# ProPrj__mini-c3_2025-12-10.net
KiCad netlist of a schematic drawn in EasyEDA Pro
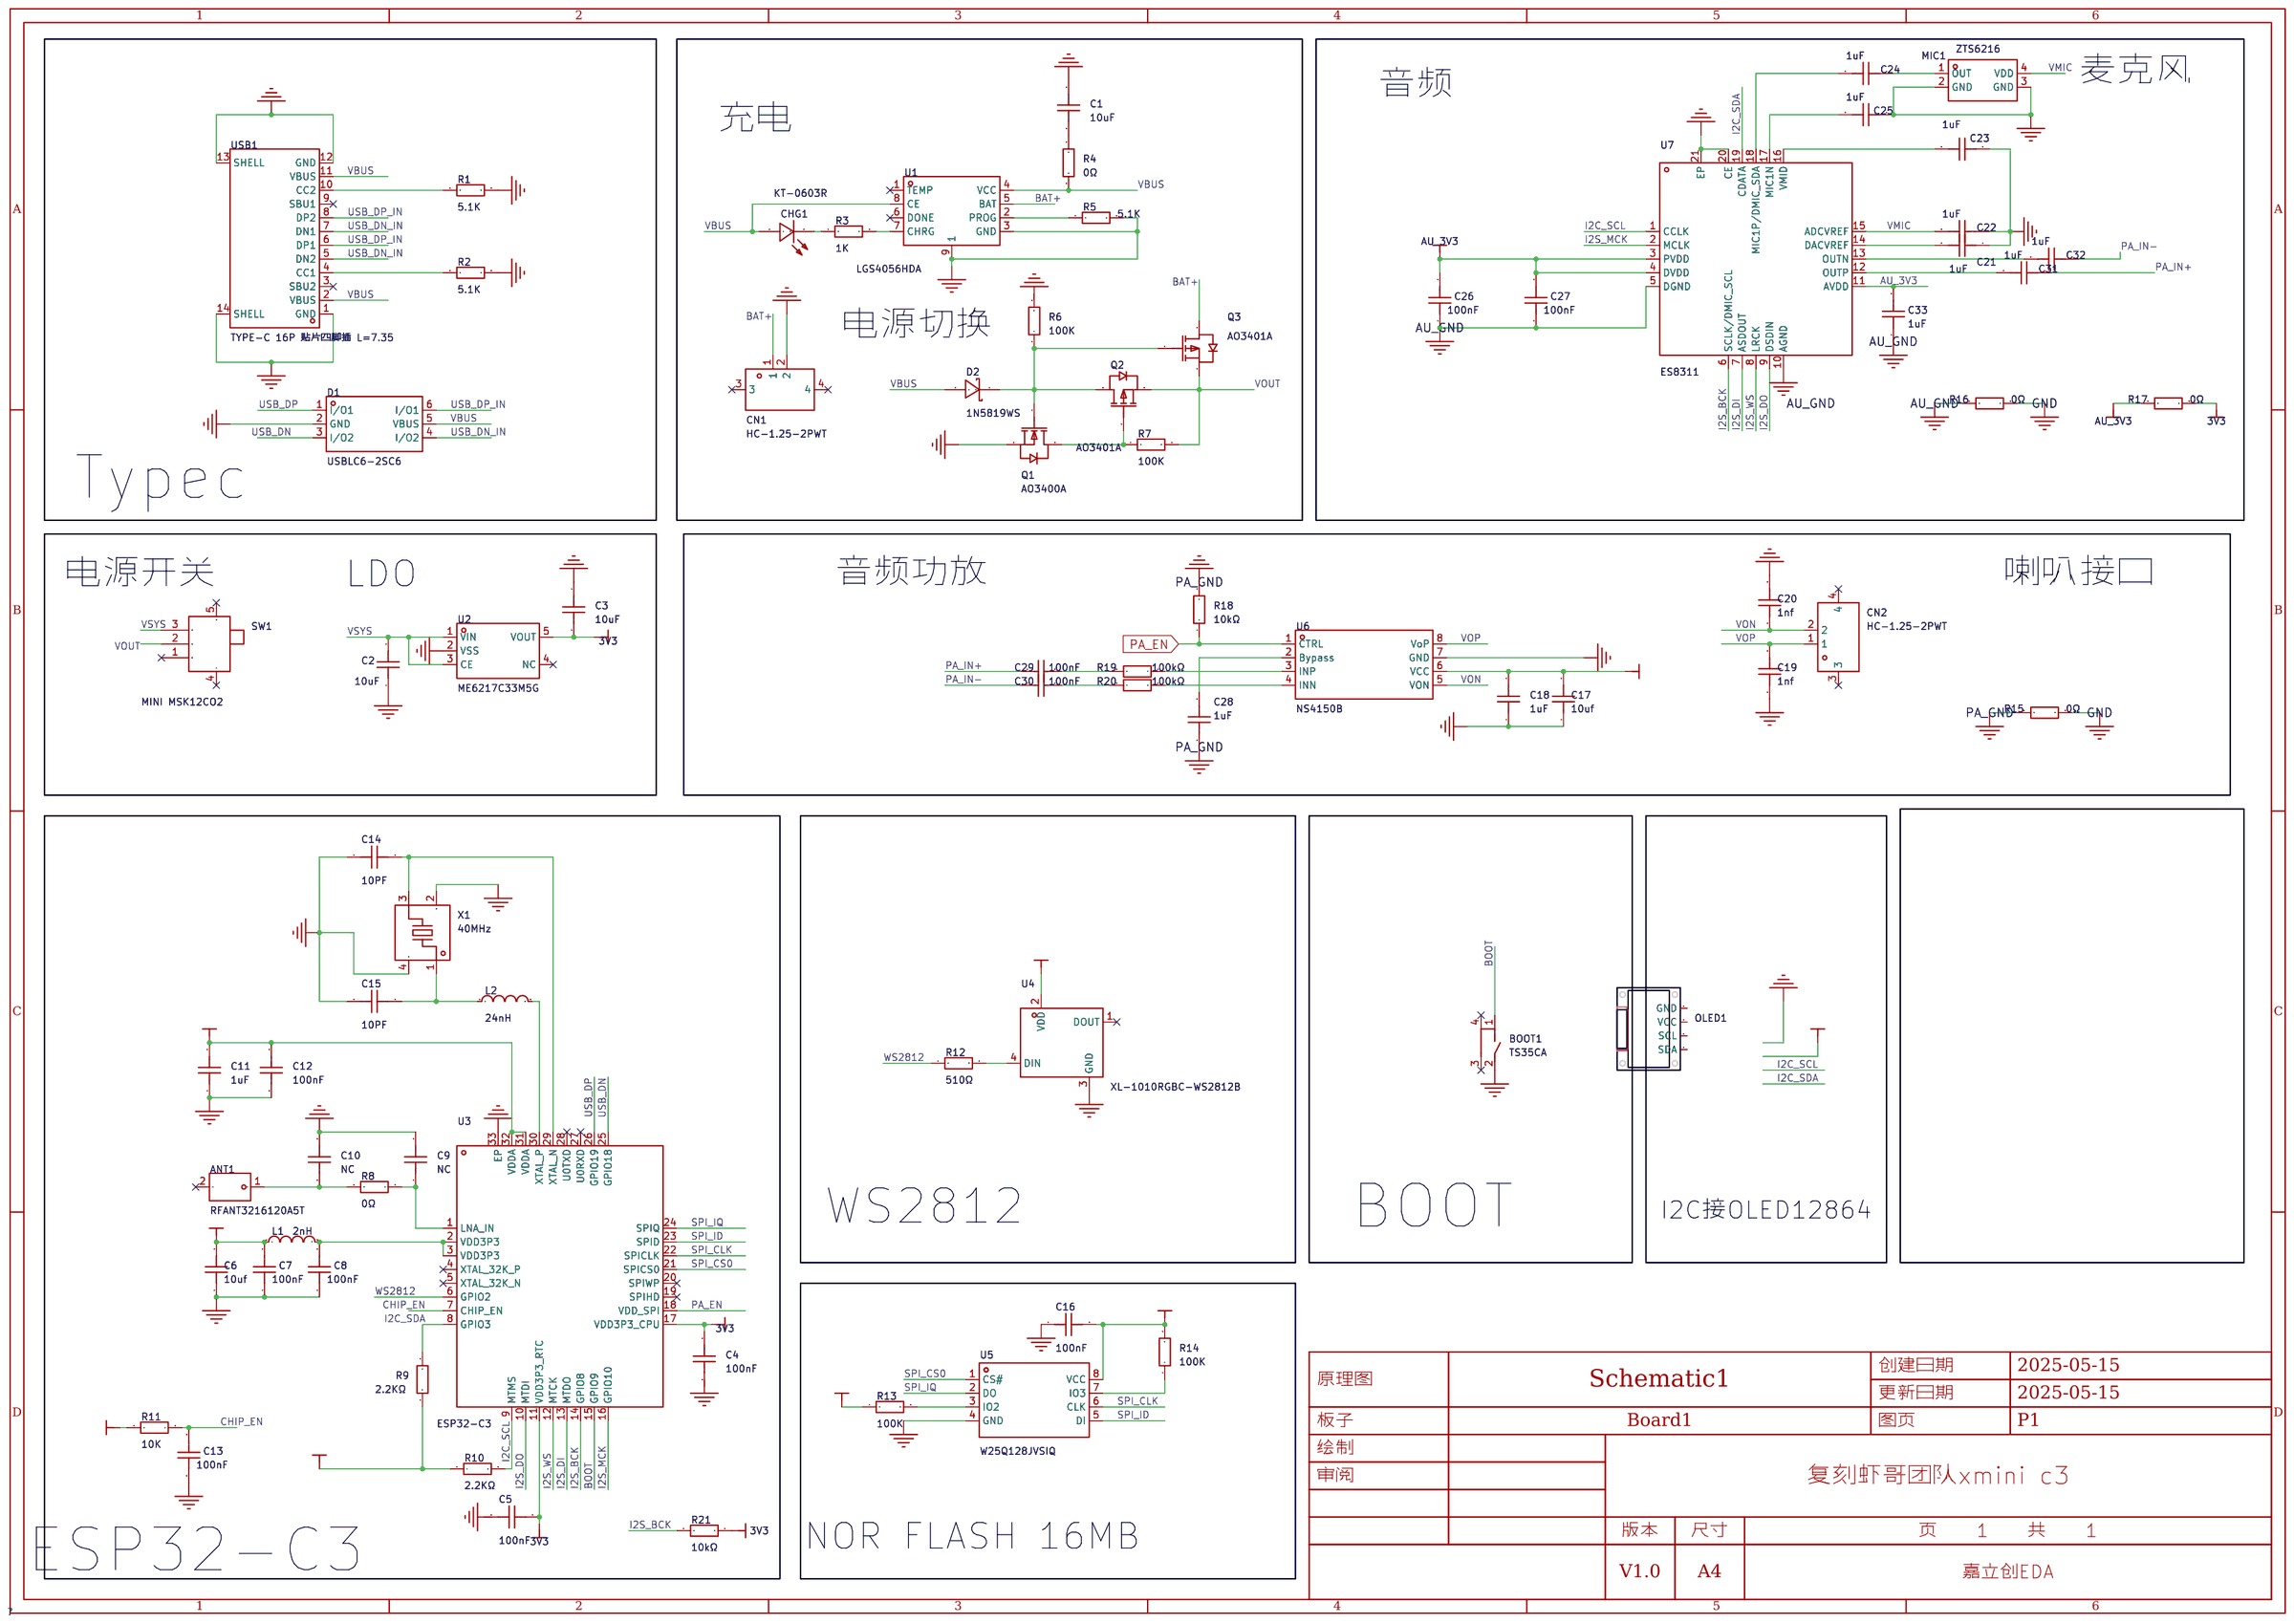
[diagram p0: schematic sheet]

(export (version "E")
  (design (tool "Eeschema 10.0.6"))
  (components
    (comp (ref "ANT1")
      (value "RFANT3216120A5T")
      (footprint "easyedapro:FILTER-SMD_1206-2P-L3.2-W1.6-L")
      (fields (field (name "Manufacturer") "Walsin(华新科)"))
      (libsource (lib "easyedapro") (part "RFANT3216120A5T"))
    )
    (comp (ref "BOOT1")
      (value "TS35CA")
      (footprint "easyedapro:KEY-SMD_TS35CA")
      (fields (field (name "Manufacturer") "SHOU HAN(首韩)"))
      (libsource (lib "easyedapro") (part "TS35CA"))
    )
    (comp (ref "C1")
      (value "10uF")
      (footprint "easyedapro:C0402")
      (libsource (lib "easyedapro") (part "CapAcitance"))
    )
    (comp (ref "C2")
      (value "10uF")
      (footprint "easyedapro:C0402")
      (libsource (lib "easyedapro") (part "CapAcitance"))
    )
    (comp (ref "C3")
      (value "10uF")
      (footprint "easyedapro:C0402")
      (libsource (lib "easyedapro") (part "CapAcitance"))
    )
    (comp (ref "C4")
      (value "100nF")
      (footprint "easyedapro:C0402")
      (libsource (lib "easyedapro") (part "CapAcitance"))
    )
    (comp (ref "C5")
      (value "100nF")
      (footprint "easyedapro:C0402")
      (libsource (lib "easyedapro") (part "CapAcitance"))
    )
    (comp (ref "C6")
      (value "10uf")
      (footprint "easyedapro:C0402")
      (libsource (lib "easyedapro") (part "CapAcitance"))
    )
    (comp (ref "C7")
      (value "100nF")
      (footprint "easyedapro:C0402")
      (libsource (lib "easyedapro") (part "CapAcitance"))
    )
    (comp (ref "C8")
      (value "100nF")
      (footprint "easyedapro:C0402")
      (libsource (lib "easyedapro") (part "CapAcitance"))
    )
    (comp (ref "C9")
      (value "NC")
      (footprint "easyedapro:C0402")
      (libsource (lib "easyedapro") (part "CapAcitance"))
    )
    (comp (ref "C10")
      (value "NC")
      (footprint "easyedapro:C0402")
      (libsource (lib "easyedapro") (part "CapAcitance"))
    )
    (comp (ref "C11")
      (value "1uF")
      (footprint "easyedapro:C0402")
      (libsource (lib "easyedapro") (part "CapAcitance"))
    )
    (comp (ref "C12")
      (value "100nF")
      (footprint "easyedapro:C0402")
      (libsource (lib "easyedapro") (part "CapAcitance"))
    )
    (comp (ref "C13")
      (value "100nF")
      (footprint "easyedapro:C0402")
      (libsource (lib "easyedapro") (part "CapAcitance"))
    )
    (comp (ref "C14")
      (value "10PF")
      (footprint "easyedapro:C0402")
      (libsource (lib "easyedapro") (part "CapAcitance"))
    )
    (comp (ref "C15")
      (value "10PF")
      (footprint "easyedapro:C0402")
      (libsource (lib "easyedapro") (part "CapAcitance"))
    )
    (comp (ref "C16")
      (value "100nF")
      (footprint "easyedapro:C0402")
      (libsource (lib "easyedapro") (part "CapAcitance"))
    )
    (comp (ref "C17")
      (value "10uf")
      (footprint "easyedapro:C0402")
      (libsource (lib "easyedapro") (part "CapAcitance"))
    )
    (comp (ref "C18")
      (value "1uF")
      (footprint "easyedapro:C0402")
      (libsource (lib "easyedapro") (part "CapAcitance"))
    )
    (comp (ref "C19")
      (value "1nf")
      (footprint "easyedapro:C0402")
      (libsource (lib "easyedapro") (part "CapAcitance"))
    )
    (comp (ref "C20")
      (value "1nf")
      (footprint "easyedapro:C0402")
      (libsource (lib "easyedapro") (part "CapAcitance"))
    )
    (comp (ref "C21")
      (value "1uF")
      (footprint "easyedapro:C0402")
      (libsource (lib "easyedapro") (part "CapAcitance"))
    )
    (comp (ref "C22")
      (value "1uF")
      (footprint "easyedapro:C0402")
      (libsource (lib "easyedapro") (part "CapAcitance"))
    )
    (comp (ref "C23")
      (value "1uF")
      (footprint "easyedapro:C0402")
      (libsource (lib "easyedapro") (part "CapAcitance"))
    )
    (comp (ref "C24")
      (value "1uF")
      (footprint "easyedapro:C0402")
      (libsource (lib "easyedapro") (part "CapAcitance"))
    )
    (comp (ref "C25")
      (value "1uF")
      (footprint "easyedapro:C0402")
      (libsource (lib "easyedapro") (part "CapAcitance"))
    )
    (comp (ref "C26")
      (value "100nF")
      (footprint "easyedapro:C0402")
      (libsource (lib "easyedapro") (part "CapAcitance"))
    )
    (comp (ref "C27")
      (value "100nF")
      (footprint "easyedapro:C0402")
      (libsource (lib "easyedapro") (part "CapAcitance"))
    )
    (comp (ref "C28")
      (value "1uF")
      (footprint "easyedapro:C0402")
      (fields
        (field (name "Manufacturer Part") "CL05A105KA5NQNC")
        (field (name "Manufacturer") "SAMSUNG(三星)")
      )
      (libsource (lib "easyedapro") (part "CL05A105KA5NQNC"))
    )
    (comp (ref "C29")
      (value "100nF")
      (footprint "easyedapro:C0402")
      (fields
        (field (name "Manufacturer Part") "CL05B104KO5NNNC")
        (field (name "Manufacturer") "SAMSUNG(三星)")
      )
      (libsource (lib "easyedapro") (part "CL05B104KO5NNNC"))
    )
    (comp (ref "C30")
      (value "100nF")
      (footprint "easyedapro:C0402")
      (fields
        (field (name "Manufacturer Part") "CL05B104KO5NNNC")
        (field (name "Manufacturer") "SAMSUNG(三星)")
      )
      (libsource (lib "easyedapro") (part "CL05B104KO5NNNC"))
    )
    (comp (ref "C31")
      (value "1uF")
      (footprint "easyedapro:C0402")
      (libsource (lib "easyedapro") (part "CapAcitance"))
    )
    (comp (ref "C32")
      (value "1uF")
      (footprint "easyedapro:C0402")
      (libsource (lib "easyedapro") (part "CapAcitance"))
    )
    (comp (ref "C33")
      (value "1uF")
      (footprint "easyedapro:C0402")
      (fields
        (field (name "Manufacturer Part") "CL05A105KA5NQNC")
        (field (name "Manufacturer") "SAMSUNG(三星)")
      )
      (libsource (lib "easyedapro") (part "CL05A105KA5NQNC"))
    )
    (comp (ref "CHG1")
      (value "KT-0603R")
      (footprint "easyedapro:LED0603-RD")
      (fields (field (name "Manufacturer") "KENTO"))
      (libsource (lib "easyedapro") (part "KT-0603R"))
    )
    (comp (ref "CN1")
      (value "HC-1.25-2PWT")
      (footprint "easyedapro:CONN-SMD_2P-P1.25-HC-1.25-2PWT")
      (fields (field (name "Manufacturer") "HCTL(华灿天禄)"))
      (libsource (lib "easyedapro") (part "HC-1.25-2PWT"))
    )
    (comp (ref "CN2")
      (value "HC-1.25-2PWT")
      (footprint "easyedapro:CONN-SMD_2P-P1.25-HC-1.25-2PWT")
      (fields (field (name "Manufacturer") "HCTL(华灿天禄)"))
      (libsource (lib "easyedapro") (part "HC-1.25-2PWT"))
    )
    (comp (ref "D1")
      (value "USBLC6-2SC6")
      (footprint "easyedapro:SOT-23-6_L2.9-W1.6-P0.95-LS2.8-BL")
      (fields (field (name "Manufacturer") "UMW(友台半导体)"))
      (libsource (lib "easyedapro") (part "USBLC6-2SC6_C2687116"))
    )
    (comp (ref "D2")
      (value "1N5819WS")
      (footprint "easyedapro:SOD-323_L1.8-W1.3-LS2.5-RD")
      (fields (field (name "Manufacturer") "Hottech(合科泰)"))
      (libsource (lib "easyedapro") (part "1N5819WS"))
    )
    (comp (ref "L1")
      (value "2nH")
      (footprint "easyedapro:L0402")
      (libsource (lib "easyedapro") (part "SDCL1005C10NJTDFM01"))
    )
    (comp (ref "L2")
      (value "24nH")
      (footprint "easyedapro:L0402")
      (libsource (lib "easyedapro") (part "SDCL1005C10NJTDFM01"))
    )
    (comp (ref "MIC1")
      (value "ZTS6216")
      (footprint "easyedapro:MIC-SMD_4P-L2.8-W1.9-P1.84-TL")
      (description "方向:全指向;信噪比:65dB;灵敏度:-38dB;阻抗:100Ω;")
      (fields (field (name "Manufacturer") "ZILLTEK(钰太)"))
      (libsource (lib "easyedapro") (part "ZTS6216"))
    )
    (comp (ref "OLED1")
      (value "~")
      (footprint "easyedapro:0.96OLED_4P")
      (libsource (lib "easyedapro") (part "0.96OLED模块_4P"))
    )
    (comp (ref "Q1")
      (value "AO3400A")
      (footprint "easyedapro:SOT-23-3_L2.9-W1.3-P1.90-LS2.4-BR")
      (fields (field (name "Manufacturer") "AOS"))
      (libsource (lib "easyedapro") (part "AO3400A"))
    )
    (comp (ref "Q2")
      (value "AO3401A")
      (footprint "easyedapro:SOT-23_L2.9-W1.3-P1.90-LS2.4-BR")
      (fields (field (name "Manufacturer") "AOS"))
      (libsource (lib "easyedapro") (part "AO3401A"))
    )
    (comp (ref "Q3")
      (value "AO3401A")
      (footprint "easyedapro:SOT-23_L2.9-W1.3-P1.90-LS2.4-BR")
      (fields (field (name "Manufacturer") "AOS"))
      (libsource (lib "easyedapro") (part "AO3401A"))
    )
    (comp (ref "R1") (value "5.1K") (footprint "easyedapro:R0402") (libsource (lib "easyedapro") (part "电阻")))
    (comp (ref "R2") (value "5.1K") (footprint "easyedapro:R0402") (libsource (lib "easyedapro") (part "电阻")))
    (comp (ref "R3") (value "1K") (footprint "easyedapro:R0402") (libsource (lib "easyedapro") (part "电阻")))
    (comp (ref "R4") (value "0Ω") (footprint "easyedapro:R0402") (libsource (lib "easyedapro") (part "电阻")))
    (comp (ref "R5") (value "5.1K") (footprint "easyedapro:R0402") (libsource (lib "easyedapro") (part "电阻")))
    (comp (ref "R6") (value "100K") (footprint "easyedapro:R0402") (libsource (lib "easyedapro") (part "电阻")))
    (comp (ref "R7") (value "100K") (footprint "easyedapro:R0402") (libsource (lib "easyedapro") (part "电阻")))
    (comp (ref "R8") (value "0Ω") (footprint "easyedapro:R0402") (libsource (lib "easyedapro") (part "电阻")))
    (comp (ref "R9")
      (value "2.2KΩ")
      (footprint "easyedapro:R0402")
      (libsource (lib "easyedapro") (part "电阻"))
    )
    (comp (ref "R10")
      (value "2.2KΩ")
      (footprint "easyedapro:R0402")
      (libsource (lib "easyedapro") (part "电阻"))
    )
    (comp (ref "R11") (value "10K") (footprint "easyedapro:R0402") (libsource (lib "easyedapro") (part "电阻")))
    (comp (ref "R12")
      (value "510Ω")
      (footprint "easyedapro:R0402")
      (libsource (lib "easyedapro") (part "电阻"))
    )
    (comp (ref "R13")
      (value "100K")
      (footprint "easyedapro:R0402")
      (libsource (lib "easyedapro") (part "电阻"))
    )
    (comp (ref "R14")
      (value "100K")
      (footprint "easyedapro:R0402")
      (libsource (lib "easyedapro") (part "电阻"))
    )
    (comp (ref "R15")
      (value "0Ω")
      (footprint "easyedapro:R0402")
      (fields
        (field (name "Manufacturer Part") "0402WGF0000TCE")
        (field (name "Manufacturer") "UNI-ROYAL(厚声)")
      )
      (libsource (lib "easyedapro") (part "0402WGF0000TCE"))
    )
    (comp (ref "R16")
      (value "0Ω")
      (footprint "easyedapro:R0402")
      (fields
        (field (name "Manufacturer Part") "0402WGF0000TCE")
        (field (name "Manufacturer") "UNI-ROYAL(厚声)")
      )
      (libsource (lib "easyedapro") (part "0402WGF0000TCE"))
    )
    (comp (ref "R17")
      (value "0Ω")
      (footprint "easyedapro:R0402")
      (fields
        (field (name "Manufacturer Part") "0402WGF0000TCE")
        (field (name "Manufacturer") "UNI-ROYAL(厚声)")
      )
      (libsource (lib "easyedapro") (part "0402WGF0000TCE"))
    )
    (comp (ref "R18")
      (value "10kΩ")
      (footprint "easyedapro:R0402")
      (fields
        (field (name "Manufacturer Part") "0402WGF1002TCE")
        (field (name "Manufacturer") "UNI-ROYAL(厚声)")
      )
      (libsource (lib "easyedapro") (part "0402WGF1002TCE"))
    )
    (comp (ref "R19")
      (value "100kΩ")
      (footprint "easyedapro:R0402")
      (fields
        (field (name "Manufacturer Part") "0402WGF1003TCE")
        (field (name "Manufacturer") "UNI-ROYAL(厚声)")
      )
      (libsource (lib "easyedapro") (part "0402WGF1003TCE"))
    )
    (comp (ref "R20")
      (value "100kΩ")
      (footprint "easyedapro:R0402")
      (fields
        (field (name "Manufacturer Part") "0402WGF1003TCE")
        (field (name "Manufacturer") "UNI-ROYAL(厚声)")
      )
      (libsource (lib "easyedapro") (part "0402WGF1003TCE"))
    )
    (comp (ref "R21")
      (value "10kΩ")
      (footprint "easyedapro:R0402")
      (fields
        (field (name "Manufacturer Part") "0402WGF1002TCE")
        (field (name "Manufacturer") "UNI-ROYAL(厚声)")
      )
      (libsource (lib "easyedapro") (part "0402WGF1002TCE"))
    )
    (comp (ref "SW1")
      (value "MINI MSK12CO2")
      (footprint "easyedapro:SW-SMD_MSK12CO2")
      (fields (field (name "Manufacturer") "SHOU HAN(首韩)"))
      (libsource (lib "easyedapro") (part "MINI MSK12CO2"))
    )
    (comp (ref "U1")
      (value "LGS4056HDA")
      (footprint "easyedapro:DFN-8_L2.0-W2.0-P0.50-TL-EP1.6")
      (fields (field (name "Manufacturer") "Legend-Si(棱晶半导体)"))
      (libsource (lib "easyedapro") (part "LGS4056H"))
    )
    (comp (ref "U2")
      (value "ME6217C33M5G")
      (footprint "easyedapro:SOT-23-5_L3.0-W1.7-P0.95-LS2.8-BR")
      (fields (field (name "Manufacturer") "MICRONE(南京微盟)"))
      (libsource (lib "easyedapro") (part "ME6217C33M5G"))
    )
    (comp (ref "U3")
      (value "ESP32-C3")
      (footprint "easyedapro:QFN-32_L5.0-W5.0-P0.50-TL-EP3.7")
      (fields (field (name "Manufacturer") "ESPRESSIF(乐鑫)"))
      (libsource (lib "easyedapro") (part "ESP32-C3"))
    )
    (comp (ref "U4")
      (value "XL-1010RGBC-WS2812B")
      (footprint "easyedapro:LED-SMD_4P-L1.0-W1.0-TL_XL-1010RGBC-WS2812B")
      (fields (field (name "Manufacturer") "XINGLIGHT(成兴光)"))
      (libsource (lib "easyedapro") (part "XL-1010RGBC-WS2812B"))
    )
    (comp (ref "U5")
      (value "W25Q128JVSIQ")
      (footprint "easyedapro:SOIC-8_L5.3-W5.3-P1.27-LS8.0-BL")
      (fields (field (name "Manufacturer") "WINBOND(华邦)"))
      (libsource (lib "easyedapro") (part "W25Q128JVSIQTR"))
    )
    (comp (ref "U6")
      (value "NS4150B")
      (footprint "easyedapro:MSOP-8_L3.0-W3.0-P0.65-LS5.0-BL")
      (fields (field (name "Manufacturer") "Nsiway(纳芯威)"))
      (libsource (lib "easyedapro") (part "NS4150"))
    )
    (comp (ref "U7")
      (value "ES8311")
      (footprint "easyedapro:WQFN-20_L3.0-W3.0-P0.40-BL-EP1.7")
      (fields (field (name "Manufacturer") "Everest-semi(顺芯)"))
      (libsource (lib "easyedapro") (part "ES8311"))
    )
    (comp (ref "USB1")
      (value "TYPE-C 16P 贴片四脚插 L=7.35")
      (footprint "easyedapro:USB-C-SMD_TYPE-C-6PIN-2MD-073")
      (libsource (lib "easyedapro") (part "TYPE-C 16P 贴片四脚插 L=7.35"))
    )
    (comp (ref "X1")
      (value "40MHz")
      (footprint "easyedapro:CRYSTAL-SMD_4P-L2.5-W2.0-BL")
      (fields (field (name "Manufacturer Part") "X252040MMB4SI") (field (name "Manufacturer") "YXC(扬兴晶振)"))
      (libsource (lib "easyedapro") (part "X252040MMB4SI"))
    )
  )
  (nets
    (net (code "1") (name "/BAT+") (class "Default")
      (node (ref "CN1") (pin "1") (pinfunction "1_1") (pintype "unspecified"))
      (node (ref "Q3") (pin "3") (pinfunction "D_3") (pintype "unspecified"))
      (node (ref "U1") (pin "5") (pinfunction "BAT_5") (pintype "unspecified"))
    )
    (net (code "2") (name "/BOOT") (class "Default")
      (node (ref "BOOT1") (pin "1") (pinfunction "1_1") (pintype "unspecified"))
      (node (ref "U3") (pin "15") (pinfunction "GPIO9_15") (pintype "unspecified"))
    )
    (net (code "3") (name "/CHIP_EN") (class "Default")
      (node (ref "C13") (pin "2") (pinfunction "2_2") (pintype "input"))
      (node (ref "R11") (pin "2") (pinfunction "2_2") (pintype "input"))
      (node (ref "U3") (pin "7") (pinfunction "CHIP_EN_7") (pintype "unspecified"))
    )
    (net (code "4") (name "/I2C_SCL") (class "Default")
      (node (ref "R10") (pin "2") (pinfunction "2_2") (pintype "input"))
      (node (ref "U3") (pin "9") (pinfunction "MTMS_9") (pintype "unspecified"))
      (node (ref "U7") (pin "1") (pinfunction "CCLK_1") (pintype "input"))
    )
    (net (code "5") (name "/I2C_SDA") (class "Default")
      (node (ref "R9") (pin "2") (pinfunction "2_2") (pintype "input"))
      (node (ref "U3") (pin "8") (pinfunction "GPIO3_8") (pintype "unspecified"))
      (node (ref "U7") (pin "19") (pinfunction "CDATA_19") (pintype "input"))
    )
    (net (code "6") (name "/I2S_BCK") (class "Default")
      (node (ref "R21") (pin "2") (pinfunction "2_2") (pintype "input"))
      (node (ref "U3") (pin "14") (pinfunction "GPIO8_14") (pintype "unspecified"))
      (node (ref "U7") (pin "6") (pinfunction "SCLK/DMIC_SCL_6") (pintype "input"))
    )
    (net (code "7") (name "/I2S_DI") (class "Default")
      (node (ref "U3") (pin "13") (pinfunction "MTDO_13") (pintype "unspecified"))
      (node (ref "U7") (pin "7") (pinfunction "ASDOUT_7") (pintype "input"))
    )
    (net (code "8") (name "/I2S_DO") (class "Default")
      (node (ref "U3") (pin "10") (pinfunction "MTDI_10") (pintype "unspecified"))
      (node (ref "U7") (pin "9") (pinfunction "DSDIN_9") (pintype "input"))
    )
    (net (code "9") (name "/I2S_MCK") (class "Default")
      (node (ref "U3") (pin "16") (pinfunction "GPIO10_16") (pintype "unspecified"))
      (node (ref "U7") (pin "2") (pinfunction "MCLK_2") (pintype "input"))
    )
    (net (code "10") (name "/I2S_WS") (class "Default")
      (node (ref "U3") (pin "12") (pinfunction "MTCK_12") (pintype "unspecified"))
      (node (ref "U7") (pin "8") (pinfunction "LRCK_8") (pintype "input"))
    )
    (net (code "11") (name "/PA_IN+") (class "Default")
      (node (ref "C29") (pin "1") (pinfunction "1_1") (pintype "input"))
      (node (ref "C31") (pin "1") (pinfunction "1_1") (pintype "input"))
    )
    (net (code "12") (name "/PA_IN-") (class "Default")
      (node (ref "C30") (pin "1") (pinfunction "1_1") (pintype "input"))
      (node (ref "C32") (pin "1") (pinfunction "1_1") (pintype "input"))
    )
    (net (code "13") (name "/SPI_CLK") (class "Default")
      (node (ref "U3") (pin "22") (pinfunction "SPICLK_22") (pintype "unspecified"))
      (node (ref "U5") (pin "6") (pinfunction "CLK_6") (pintype "unspecified"))
    )
    (net (code "14") (name "/SPI_CS0") (class "Default")
      (node (ref "U3") (pin "21") (pinfunction "SPICS0_21") (pintype "unspecified"))
      (node (ref "U5") (pin "1") (pinfunction "CS#_1") (pintype "unspecified"))
    )
    (net (code "15") (name "/SPI_ID") (class "Default")
      (node (ref "U3") (pin "23") (pinfunction "SPID_23") (pintype "unspecified"))
      (node (ref "U5") (pin "5") (pinfunction "DI_5") (pintype "unspecified"))
    )
    (net (code "16") (name "/SPI_IQ") (class "Default")
      (node (ref "U3") (pin "24") (pinfunction "SPIQ_24") (pintype "unspecified"))
      (node (ref "U5") (pin "2") (pinfunction "DO_2") (pintype "unspecified"))
    )
    (net (code "17") (name "/USB_DN") (class "Default")
      (node (ref "D1") (pin "3") (pinfunction "I/O2_3") (pintype "unspecified"))
      (node (ref "U3") (pin "25") (pinfunction "GPIO18_25") (pintype "unspecified"))
    )
    (net (code "18") (name "/USB_DN_IN") (class "Default")
      (node (ref "D1") (pin "4") (pinfunction "I/O2_4") (pintype "unspecified"))
      (node (ref "USB1") (pin "5") (pinfunction "DN2_5") (pintype "unspecified"))
      (node (ref "USB1") (pin "7") (pinfunction "DN1_7") (pintype "unspecified"))
    )
    (net (code "19") (name "/USB_DP") (class "Default")
      (node (ref "D1") (pin "1") (pinfunction "I/O1_1") (pintype "unspecified"))
      (node (ref "U3") (pin "26") (pinfunction "GPIO19_26") (pintype "unspecified"))
    )
    (net (code "20") (name "/USB_DP_IN") (class "Default")
      (node (ref "D1") (pin "6") (pinfunction "I/O1_6") (pintype "unspecified"))
      (node (ref "USB1") (pin "6") (pinfunction "DP1_6") (pintype "unspecified"))
      (node (ref "USB1") (pin "8") (pinfunction "DP2_8") (pintype "unspecified"))
    )
    (net (code "21") (name "/VBUS") (class "Default")
      (node (ref "CHG1") (pin "2") (pinfunction "A_2") (pintype "unspecified"))
      (node (ref "D1") (pin "5") (pinfunction "VBUS_5") (pintype "unspecified"))
      (node (ref "D2") (pin "2") (pinfunction "A_2") (pintype "unspecified"))
      (node (ref "R4") (pin "1") (pinfunction "1_1") (pintype "input"))
      (node (ref "U1") (pin "4") (pinfunction "VCC_4") (pintype "unspecified"))
      (node (ref "U1") (pin "8") (pinfunction "CE_8") (pintype "unspecified"))
      (node (ref "USB1") (pin "11") (pinfunction "VBUS_11") (pintype "unspecified"))
      (node (ref "USB1") (pin "2") (pinfunction "VBUS_2") (pintype "unspecified"))
    )
    (net (code "22") (name "/VMIC") (class "Default")
      (node (ref "C22") (pin "2") (pinfunction "2_2") (pintype "input"))
      (node (ref "MIC1") (pin "4") (pinfunction "VDD_4") (pintype "input"))
      (node (ref "U7") (pin "15") (pinfunction "ADCVREF_15") (pintype "input"))
    )
    (net (code "23") (name "/VON") (class "Default")
      (node (ref "C20") (pin "1") (pinfunction "1_1") (pintype "input"))
      (node (ref "CN2") (pin "2") (pinfunction "2_2") (pintype "unspecified"))
      (node (ref "U6") (pin "5") (pinfunction "VON_5") (pintype "unspecified"))
    )
    (net (code "24") (name "/VOP") (class "Default")
      (node (ref "C19") (pin "2") (pinfunction "2_2") (pintype "input"))
      (node (ref "CN2") (pin "1") (pinfunction "1_1") (pintype "unspecified"))
      (node (ref "U6") (pin "8") (pinfunction "VoP_8") (pintype "unspecified"))
    )
    (net (code "25") (name "/VOUT") (class "Default")
      (node (ref "Q2") (pin "2") (pinfunction "S_2") (pintype "unspecified"))
      (node (ref "Q3") (pin "2") (pinfunction "S_2") (pintype "unspecified"))
      (node (ref "R7") (pin "2") (pinfunction "2_2") (pintype "input"))
      (node (ref "SW1") (pin "2") (pinfunction "2_2") (pintype "unspecified"))
    )
    (net (code "26") (name "/WS2812") (class "Default")
      (node (ref "R12") (pin "1") (pinfunction "1_1") (pintype "input"))
      (node (ref "U3") (pin "6") (pinfunction "GPIO2_6") (pintype "unspecified"))
    )
    (net (code "27") (name "3V3") (class "Default")
      (node (ref "C11") (pin "2") (pinfunction "2_2") (pintype "input"))
      (node (ref "C12") (pin "1") (pinfunction "1_1") (pintype "input"))
      (node (ref "C16") (pin "2") (pinfunction "2_2") (pintype "input"))
      (node (ref "C3") (pin "2") (pinfunction "2_2") (pintype "input"))
      (node (ref "C4") (pin "1") (pinfunction "1_1") (pintype "input"))
      (node (ref "C5") (pin "1") (pinfunction "1_1") (pintype "input"))
      (node (ref "C6") (pin "2") (pinfunction "2_2") (pintype "input"))
      (node (ref "C7") (pin "2") (pinfunction "2_2") (pintype "input"))
      (node (ref "L1") (pin "1") (pinfunction "1_1") (pintype "unspecified"))
      (node (ref "R10") (pin "1") (pinfunction "1_1") (pintype "input"))
      (node (ref "R11") (pin "1") (pinfunction "1_1") (pintype "input"))
      (node (ref "R13") (pin "1") (pinfunction "1_1") (pintype "input"))
      (node (ref "R14") (pin "2") (pinfunction "2_2") (pintype "input"))
      (node (ref "R17") (pin "2") (pinfunction "2_2") (pintype "input"))
      (node (ref "R21") (pin "1") (pinfunction "1_1") (pintype "input"))
      (node (ref "R9") (pin "1") (pinfunction "1_1") (pintype "input"))
      (node (ref "U2") (pin "5") (pinfunction "VOUT_5") (pintype "unspecified"))
      (node (ref "U3") (pin "11") (pinfunction "VDD3P3_RTC_11") (pintype "unspecified"))
      (node (ref "U3") (pin "17") (pinfunction "VDD3P3_CPU_17") (pintype "unspecified"))
      (node (ref "U3") (pin "31") (pinfunction "VDDA_31") (pintype "unspecified"))
      (node (ref "U3") (pin "32") (pinfunction "VDDA_32") (pintype "unspecified"))
      (node (ref "U5") (pin "8") (pinfunction "VCC_8") (pintype "unspecified"))
    )
    (net (code "28") (name "AU_3V3") (class "Default")
      (node (ref "C26") (pin "2") (pinfunction "2_2") (pintype "input"))
      (node (ref "C27") (pin "2") (pinfunction "2_2") (pintype "input"))
      (node (ref "C33") (pin "2") (pinfunction "2_2") (pintype "input"))
      (node (ref "R17") (pin "1") (pinfunction "1_1") (pintype "input"))
      (node (ref "U7") (pin "11") (pinfunction "AVDD_11") (pintype "input"))
      (node (ref "U7") (pin "3") (pinfunction "PVDD_3") (pintype "input"))
      (node (ref "U7") (pin "4") (pinfunction "DVDD_4") (pintype "input"))
    )
    (net (code "29") (name "AU_GND") (class "Default")
      (node (ref "C21") (pin "1") (pinfunction "1_1") (pintype "input"))
      (node (ref "C22") (pin "1") (pinfunction "1_1") (pintype "input"))
      (node (ref "C23") (pin "1") (pinfunction "1_1") (pintype "input"))
      (node (ref "C25") (pin "1") (pinfunction "1_1") (pintype "input"))
      (node (ref "C26") (pin "1") (pinfunction "1_1") (pintype "input"))
      (node (ref "C27") (pin "1") (pinfunction "1_1") (pintype "input"))
      (node (ref "C33") (pin "1") (pinfunction "1_1") (pintype "input"))
      (node (ref "MIC1") (pin "2") (pinfunction "GND_2") (pintype "input"))
      (node (ref "MIC1") (pin "3") (pinfunction "GND_3") (pintype "input"))
      (node (ref "R16") (pin "1") (pinfunction "1_1") (pintype "input"))
      (node (ref "U7") (pin "10") (pinfunction "AGND_10") (pintype "input"))
      (node (ref "U7") (pin "20") (pinfunction "CE_20") (pintype "input"))
      (node (ref "U7") (pin "21") (pinfunction "EP_21") (pintype "input"))
      (node (ref "U7") (pin "5") (pinfunction "DGND_5") (pintype "input"))
    )
    (net (code "30") (name "GND") (class "Default")
      (node (ref "BOOT1") (pin "2") (pinfunction "2_2") (pintype "unspecified"))
      (node (ref "C1") (pin "2") (pinfunction "2_2") (pintype "input"))
      (node (ref "C10") (pin "2") (pinfunction "2_2") (pintype "input"))
      (node (ref "C11") (pin "1") (pinfunction "1_1") (pintype "input"))
      (node (ref "C12") (pin "2") (pinfunction "2_2") (pintype "input"))
      (node (ref "C13") (pin "1") (pinfunction "1_1") (pintype "input"))
      (node (ref "C14") (pin "1") (pinfunction "1_1") (pintype "input"))
      (node (ref "C15") (pin "1") (pinfunction "1_1") (pintype "input"))
      (node (ref "C16") (pin "1") (pinfunction "1_1") (pintype "input"))
      (node (ref "C2") (pin "1") (pinfunction "1_1") (pintype "input"))
      (node (ref "C3") (pin "1") (pinfunction "1_1") (pintype "input"))
      (node (ref "C4") (pin "2") (pinfunction "2_2") (pintype "input"))
      (node (ref "C5") (pin "2") (pinfunction "2_2") (pintype "input"))
      (node (ref "C6") (pin "1") (pinfunction "1_1") (pintype "input"))
      (node (ref "C7") (pin "1") (pinfunction "1_1") (pintype "input"))
      (node (ref "C8") (pin "1") (pinfunction "1_1") (pintype "input"))
      (node (ref "C9") (pin "2") (pinfunction "2_2") (pintype "input"))
      (node (ref "CN1") (pin "2") (pinfunction "2_2") (pintype "unspecified"))
      (node (ref "D1") (pin "2") (pinfunction "GND_2") (pintype "unspecified"))
      (node (ref "Q1") (pin "2") (pinfunction "S_2") (pintype "unspecified"))
      (node (ref "R1") (pin "2") (pinfunction "2_2") (pintype "input"))
      (node (ref "R15") (pin "2") (pinfunction "2_2") (pintype "input"))
      (node (ref "R16") (pin "2") (pinfunction "2_2") (pintype "input"))
      (node (ref "R2") (pin "2") (pinfunction "2_2") (pintype "input"))
      (node (ref "R5") (pin "2") (pinfunction "2_2") (pintype "input"))
      (node (ref "R6") (pin "2") (pinfunction "2_2") (pintype "input"))
      (node (ref "U1") (pin "3") (pinfunction "GND_3") (pintype "unspecified"))
      (node (ref "U1") (pin "9") (pinfunction "1_9") (pintype "unspecified"))
      (node (ref "U2") (pin "2") (pinfunction "VSS_2") (pintype "unspecified"))
      (node (ref "U3") (pin "33") (pinfunction "EP_33") (pintype "unspecified"))
      (node (ref "U4") (pin "3") (pinfunction "GND_3") (pintype "unspecified"))
      (node (ref "U5") (pin "4") (pinfunction "GND_4") (pintype "unspecified"))
      (node (ref "USB1") (pin "1") (pinfunction "GND_1") (pintype "unspecified"))
      (node (ref "USB1") (pin "12") (pinfunction "GND_12") (pintype "unspecified"))
      (node (ref "USB1") (pin "13") (pinfunction "SHELL_13") (pintype "unspecified"))
      (node (ref "USB1") (pin "14") (pinfunction "SHELL_14") (pintype "unspecified"))
      (node (ref "X1") (pin "2") (pinfunction "GND_2") (pintype "input"))
      (node (ref "X1") (pin "4") (pinfunction "GND_4") (pintype "input"))
    )
    (net (code "31") (name "Net-(ANT1-Pad1)") (class "Default")
      (node (ref "ANT1") (pin "1") (pinfunction "1_1") (pintype "unspecified"))
      (node (ref "C10") (pin "1") (pinfunction "1_1") (pintype "input"))
      (node (ref "R8") (pin "1") (pinfunction "1_1") (pintype "input"))
    )
    (net (code "32") (name "Net-(C1-Pad1)") (class "Default")
      (node (ref "C1") (pin "1") (pinfunction "1_1") (pintype "input"))
      (node (ref "R4") (pin "2") (pinfunction "2_2") (pintype "input"))
    )
    (net (code "33") (name "Net-(C8-Pad2)") (class "Default")
      (node (ref "C8") (pin "2") (pinfunction "2_2") (pintype "input"))
      (node (ref "L1") (pin "2") (pinfunction "2_2") (pintype "unspecified"))
      (node (ref "U3") (pin "2") (pinfunction "VDD3P3_2") (pintype "unspecified"))
      (node (ref "U3") (pin "3") (pinfunction "VDD3P3_3") (pintype "unspecified"))
    )
    (net (code "34") (name "Net-(C15-Pad2)") (class "Default")
      (node (ref "C15") (pin "2") (pinfunction "2_2") (pintype "input"))
      (node (ref "L2") (pin "1") (pinfunction "1_1") (pintype "unspecified"))
      (node (ref "X1") (pin "1") (pinfunction "1_1") (pintype "input"))
    )
    (net (code "35") (name "Net-(C29-Pad2)") (class "Default")
      (node (ref "C29") (pin "2") (pinfunction "2_2") (pintype "input"))
      (node (ref "R19") (pin "2") (pinfunction "2_2") (pintype "input"))
    )
    (net (code "36") (name "Net-(C30-Pad2)") (class "Default")
      (node (ref "C30") (pin "2") (pinfunction "2_2") (pintype "input"))
      (node (ref "R20") (pin "2") (pinfunction "2_2") (pintype "input"))
    )
    (net (code "37") (name "Net-(CHG1-K)") (class "Default")
      (node (ref "CHG1") (pin "1") (pinfunction "K_1") (pintype "unspecified"))
      (node (ref "R3") (pin "1") (pinfunction "1_1") (pintype "input"))
    )
    (net (code "38") (name "Net-(D2-K)") (class "Default")
      (node (ref "D2") (pin "1") (pinfunction "K_1") (pintype "unspecified"))
      (node (ref "Q1") (pin "1") (pinfunction "G_1") (pintype "unspecified"))
      (node (ref "Q2") (pin "3") (pinfunction "D_3") (pintype "unspecified"))
      (node (ref "Q3") (pin "1") (pinfunction "G_1") (pintype "unspecified"))
      (node (ref "R6") (pin "1") (pinfunction "1_1") (pintype "input"))
    )
    (net (code "39") (name "Net-(MIC1-OUT)") (class "Default")
      (node (ref "C24") (pin "1") (pinfunction "1_1") (pintype "input"))
      (node (ref "MIC1") (pin "1") (pinfunction "OUT_1") (pintype "input"))
    )
    (net (code "40") (name "Net-(Q1-D)") (class "Default")
      (node (ref "Q1") (pin "3") (pinfunction "D_3") (pintype "unspecified"))
      (node (ref "Q2") (pin "1") (pinfunction "G_1") (pintype "unspecified"))
      (node (ref "R7") (pin "1") (pinfunction "1_1") (pintype "input"))
    )
    (net (code "41") (name "Net-(U1-CHRG)") (class "Default")
      (node (ref "R3") (pin "2") (pinfunction "2_2") (pintype "input"))
      (node (ref "U1") (pin "7") (pinfunction "CHRG_7") (pintype "unspecified"))
    )
    (net (code "42") (name "Net-(U1-PROG)") (class "Default")
      (node (ref "R5") (pin "1") (pinfunction "1_1") (pintype "input"))
      (node (ref "U1") (pin "2") (pinfunction "PROG_2") (pintype "unspecified"))
    )
    (net (code "43") (name "Net-(U3-LNA_IN)") (class "Default")
      (node (ref "C9") (pin "1") (pinfunction "1_1") (pintype "input"))
      (node (ref "R8") (pin "2") (pinfunction "2_2") (pintype "input"))
      (node (ref "U3") (pin "1") (pinfunction "LNA_IN_1") (pintype "unspecified"))
    )
    (net (code "44") (name "Net-(U3-XTAL_N)") (class "Default")
      (node (ref "C14") (pin "2") (pinfunction "2_2") (pintype "input"))
      (node (ref "U3") (pin "29") (pinfunction "XTAL_N_29") (pintype "unspecified"))
      (node (ref "X1") (pin "3") (pinfunction "3_3") (pintype "input"))
    )
    (net (code "45") (name "Net-(U3-XTAL_P)") (class "Default")
      (node (ref "L2") (pin "2") (pinfunction "2_2") (pintype "unspecified"))
      (node (ref "U3") (pin "30") (pinfunction "XTAL_P_30") (pintype "unspecified"))
    )
    (net (code "46") (name "Net-(U4-DIN)") (class "Default")
      (node (ref "R12") (pin "2") (pinfunction "2_2") (pintype "input"))
      (node (ref "U4") (pin "4") (pinfunction "DIN_4") (pintype "unspecified"))
    )
    (net (code "47") (name "Net-(U5-IO2)") (class "Default")
      (node (ref "R13") (pin "2") (pinfunction "2_2") (pintype "input"))
      (node (ref "U5") (pin "3") (pinfunction "IO2_3") (pintype "unspecified"))
    )
    (net (code "48") (name "Net-(U5-IO3)") (class "Default")
      (node (ref "R14") (pin "1") (pinfunction "1_1") (pintype "input"))
      (node (ref "U5") (pin "7") (pinfunction "IO3_7") (pintype "unspecified"))
    )
    (net (code "49") (name "Net-(U6-Bypass)") (class "Default")
      (node (ref "C28") (pin "2") (pinfunction "2_2") (pintype "input"))
      (node (ref "U6") (pin "2") (pinfunction "Bypass_2") (pintype "unspecified"))
    )
    (net (code "50") (name "Net-(U6-INN)") (class "Default")
      (node (ref "R20") (pin "1") (pinfunction "1_1") (pintype "input"))
      (node (ref "U6") (pin "4") (pinfunction "INN_4") (pintype "unspecified"))
    )
    (net (code "51") (name "Net-(U6-INP)") (class "Default")
      (node (ref "R19") (pin "1") (pinfunction "1_1") (pintype "input"))
      (node (ref "U6") (pin "3") (pinfunction "INP_3") (pintype "unspecified"))
    )
    (net (code "52") (name "Net-(U7-DACVREF)") (class "Default")
      (node (ref "C21") (pin "2") (pinfunction "2_2") (pintype "input"))
      (node (ref "U7") (pin "14") (pinfunction "DACVREF_14") (pintype "input"))
    )
    (net (code "53") (name "Net-(U7-MIC1N)") (class "Default")
      (node (ref "C25") (pin "2") (pinfunction "2_2") (pintype "input"))
      (node (ref "U7") (pin "17") (pinfunction "MIC1N_17") (pintype "input"))
    )
    (net (code "54") (name "Net-(U7-MIC1P{slash}DMIC_SDA)") (class "Default")
      (node (ref "C24") (pin "2") (pinfunction "2_2") (pintype "input"))
      (node (ref "U7") (pin "18") (pinfunction "MIC1P/DMIC_SDA_18") (pintype "input"))
    )
    (net (code "55") (name "Net-(U7-OUTN)") (class "Default")
      (node (ref "C32") (pin "2") (pinfunction "2_2") (pintype "input"))
      (node (ref "U7") (pin "13") (pinfunction "OUTN_13") (pintype "input"))
    )
    (net (code "56") (name "Net-(U7-OUTP)") (class "Default")
      (node (ref "C31") (pin "2") (pinfunction "2_2") (pintype "input"))
      (node (ref "U7") (pin "12") (pinfunction "OUTP_12") (pintype "input"))
    )
    (net (code "57") (name "Net-(U7-VMID)") (class "Default")
      (node (ref "C23") (pin "2") (pinfunction "2_2") (pintype "input"))
      (node (ref "U7") (pin "16") (pinfunction "VMID_16") (pintype "input"))
    )
    (net (code "58") (name "Net-(USB1-CC1)") (class "Default")
      (node (ref "R2") (pin "1") (pinfunction "1_1") (pintype "input"))
      (node (ref "USB1") (pin "4") (pinfunction "CC1_4") (pintype "unspecified"))
    )
    (net (code "59") (name "Net-(USB1-CC2)") (class "Default")
      (node (ref "R1") (pin "1") (pinfunction "1_1") (pintype "input"))
      (node (ref "USB1") (pin "10") (pinfunction "CC2_10") (pintype "unspecified"))
    )
    (net (code "60") (name "PA-GND") (class "Default")
      (node (ref "C19") (pin "1") (pinfunction "1_1") (pintype "input"))
    )
    (net (code "61") (name "PA_EN") (class "Default")
      (node (ref "R18") (pin "1") (pinfunction "1_1") (pintype "input"))
      (node (ref "U3") (pin "18") (pinfunction "VDD_SPI_18") (pintype "unspecified"))
      (node (ref "U6") (pin "1") (pinfunction "CTRL_1") (pintype "unspecified"))
    )
    (net (code "62") (name "PA_GND") (class "Default")
      (node (ref "C17") (pin "1") (pinfunction "1_1") (pintype "input"))
      (node (ref "C18") (pin "1") (pinfunction "1_1") (pintype "input"))
      (node (ref "C20") (pin "2") (pinfunction "2_2") (pintype "input"))
      (node (ref "C28") (pin "1") (pinfunction "1_1") (pintype "input"))
      (node (ref "R15") (pin "1") (pinfunction "1_1") (pintype "input"))
      (node (ref "R18") (pin "2") (pinfunction "2_2") (pintype "input"))
      (node (ref "U6") (pin "7") (pinfunction "GND_7") (pintype "unspecified"))
    )
    (net (code "63") (name "VSYS") (class "Default")
      (node (ref "C17") (pin "2") (pinfunction "2_2") (pintype "input"))
      (node (ref "C18") (pin "2") (pinfunction "2_2") (pintype "input"))
      (node (ref "C2") (pin "2") (pinfunction "2_2") (pintype "input"))
      (node (ref "SW1") (pin "3") (pinfunction "3_3") (pintype "unspecified"))
      (node (ref "U2") (pin "1") (pinfunction "VIN_1") (pintype "unspecified"))
      (node (ref "U2") (pin "3") (pinfunction "CE_3") (pintype "unspecified"))
      (node (ref "U4") (pin "2") (pinfunction "VDD_2") (pintype "unspecified"))
      (node (ref "U6") (pin "6") (pinfunction "VCC_6") (pintype "unspecified"))
    )
    (net (code "64") (name "unconnected-(ANT1-Pad2)") (class "Default")
      (node (ref "ANT1") (pin "2") (pinfunction "2_2") (pintype "unspecified+no_connect"))
    )
    (net (code "65") (name "unconnected-(BOOT1-Pad3)") (class "Default")
      (node (ref "BOOT1") (pin "3") (pinfunction "3_3") (pintype "unspecified+no_connect"))
    )
    (net (code "66") (name "unconnected-(BOOT1-Pad4)") (class "Default")
      (node (ref "BOOT1") (pin "4") (pinfunction "4_4") (pintype "unspecified+no_connect"))
    )
    (net (code "67") (name "unconnected-(CN1-Pad3)") (class "Default")
      (node (ref "CN1") (pin "3") (pinfunction "3_3") (pintype "unspecified+no_connect"))
    )
    (net (code "68") (name "unconnected-(CN1-Pad4)") (class "Default")
      (node (ref "CN1") (pin "4") (pinfunction "4_4") (pintype "unspecified+no_connect"))
    )
    (net (code "69") (name "unconnected-(CN2-Pad3)") (class "Default")
      (node (ref "CN2") (pin "3") (pinfunction "3_3") (pintype "unspecified+no_connect"))
    )
    (net (code "70") (name "unconnected-(CN2-Pad4)") (class "Default")
      (node (ref "CN2") (pin "4") (pinfunction "4_4") (pintype "unspecified+no_connect"))
    )
    (net (code "71") (name "unconnected-(OLED1-GND-Pad1)") (class "Default")
      (node (ref "OLED1") (pin "1") (pinfunction "GND_1") (pintype "input"))
    )
    (net (code "72") (name "unconnected-(OLED1-SCL-Pad3)") (class "Default")
      (node (ref "OLED1") (pin "3") (pinfunction "SCL_3") (pintype "input"))
    )
    (net (code "73") (name "unconnected-(OLED1-SDA-Pad4)") (class "Default")
      (node (ref "OLED1") (pin "4") (pinfunction "SDA_4") (pintype "input"))
    )
    (net (code "74") (name "unconnected-(OLED1-VCC-Pad2)") (class "Default")
      (node (ref "OLED1") (pin "2") (pinfunction "VCC_2") (pintype "input"))
    )
    (net (code "75") (name "unconnected-(SW1-Pad1)") (class "Default")
      (node (ref "SW1") (pin "1") (pinfunction "1_1") (pintype "unspecified+no_connect"))
    )
    (net (code "76") (name "unconnected-(SW1-Pad4)") (class "Default")
      (node (ref "SW1") (pin "4") (pinfunction "4_4") (pintype "unspecified+no_connect"))
    )
    (net (code "77") (name "unconnected-(SW1-Pad5)") (class "Default")
      (node (ref "SW1") (pin "5") (pinfunction "5_5") (pintype "unspecified+no_connect"))
    )
    (net (code "78") (name "unconnected-(U1-DONE-Pad6)") (class "Default")
      (node (ref "U1") (pin "6") (pinfunction "DONE_6") (pintype "unspecified+no_connect"))
    )
    (net (code "79") (name "unconnected-(U1-TEMP-Pad1)") (class "Default")
      (node (ref "U1") (pin "1") (pinfunction "TEMP_1") (pintype "unspecified+no_connect"))
    )
    (net (code "80") (name "unconnected-(U2-NC-Pad4)") (class "Default")
      (node (ref "U2") (pin "4") (pinfunction "NC_4") (pintype "unspecified+no_connect"))
    )
    (net (code "81") (name "unconnected-(U3-SPIHD-Pad19)") (class "Default")
      (node (ref "U3") (pin "19") (pinfunction "SPIHD_19") (pintype "unspecified+no_connect"))
    )
    (net (code "82") (name "unconnected-(U3-SPIWP-Pad20)") (class "Default")
      (node (ref "U3") (pin "20") (pinfunction "SPIWP_20") (pintype "unspecified+no_connect"))
    )
    (net (code "83") (name "unconnected-(U3-U0RXD-Pad27)") (class "Default")
      (node (ref "U3") (pin "27") (pinfunction "U0RXD_27") (pintype "unspecified+no_connect"))
    )
    (net (code "84") (name "unconnected-(U3-U0TXD-Pad28)") (class "Default")
      (node (ref "U3") (pin "28") (pinfunction "U0TXD_28") (pintype "unspecified+no_connect"))
    )
    (net (code "85") (name "unconnected-(U3-XTAL_32K_N-Pad5)") (class "Default")
      (node (ref "U3") (pin "5") (pinfunction "XTAL_32K_N_5") (pintype "unspecified+no_connect"))
    )
    (net (code "86") (name "unconnected-(U3-XTAL_32K_P-Pad4)") (class "Default")
      (node (ref "U3") (pin "4") (pinfunction "XTAL_32K_P_4") (pintype "unspecified+no_connect"))
    )
    (net (code "87") (name "unconnected-(U4-DOUT-Pad1)") (class "Default")
      (node (ref "U4") (pin "1") (pinfunction "DOUT_1") (pintype "unspecified+no_connect"))
    )
    (net (code "88") (name "unconnected-(USB1-SBU1-Pad9)") (class "Default")
      (node (ref "USB1") (pin "9") (pinfunction "SBU1_9") (pintype "unspecified+no_connect"))
    )
    (net (code "89") (name "unconnected-(USB1-SBU2-Pad3)") (class "Default")
      (node (ref "USB1") (pin "3") (pinfunction "SBU2_3") (pintype "unspecified+no_connect"))
    )
  )
)
